# Filter-Stereo.net
KiCad netlist of a schematic drawn in Altium Designer
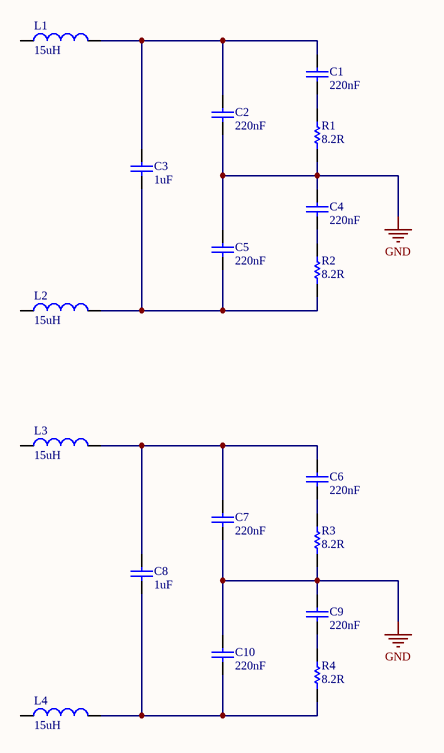
[diagram p0: Filter-Stereo.SchDoc]

(export (version "E")
  (design (tool "Eeschema 10.0.6"))
  (components
    (comp (ref "C1")
      (value "220nF")
      (footprint "CAP_RM15_W5L18")
      (description "CAP FILM 0.22UF 5% 100VDC RADIAL")
      (fields (field (name "MPN") "B32529C1224J289") (field (name "TOLERANCE") "5%"))
      (libsource (lib "micun") (part "CAP_B32529 _220nF"))
    )
    (comp (ref "C2")
      (value "220nF")
      (footprint "CAP_RM15_W5L18")
      (description "CAP FILM 0.22UF 5% 100VDC RADIAL")
      (fields (field (name "MPN") "B32529C1224J289") (field (name "TOLERANCE") "5%"))
      (libsource (lib "micun") (part "CAP_B32529 _220nF"))
    )
    (comp (ref "C3")
      (value "1uF")
      (footprint "CAP_RM5_W7.8L7.8H13")
      (description "CAP FILM 1UF 5% 100VDC RADIAL")
      (fields (field (name "MPN") "B32529D1105J289") (field (name "TOLERANCE") "5%"))
      (libsource (lib "micun") (part "CAP_B32529 _1uF"))
    )
    (comp (ref "C4")
      (value "220nF")
      (footprint "CAP_RM15_W5L18")
      (description "CAP FILM 0.22UF 5% 100VDC RADIAL")
      (fields (field (name "MPN") "B32529C1224J289") (field (name "TOLERANCE") "5%"))
      (libsource (lib "micun") (part "CAP_B32529 _220nF"))
    )
    (comp (ref "C5")
      (value "220nF")
      (footprint "CAP_RM15_W5L18")
      (description "CAP FILM 0.22UF 5% 100VDC RADIAL")
      (fields (field (name "MPN") "B32529C1224J289") (field (name "TOLERANCE") "5%"))
      (libsource (lib "micun") (part "CAP_B32529 _220nF"))
    )
    (comp (ref "C6")
      (value "220nF")
      (footprint "CAP_RM15_W5L18")
      (description "CAP FILM 0.22UF 5% 100VDC RADIAL")
      (fields (field (name "MPN") "B32529C1224J289") (field (name "TOLERANCE") "5%"))
      (libsource (lib "micun") (part "CAP_B32529 _220nF"))
    )
    (comp (ref "C7")
      (value "220nF")
      (footprint "CAP_RM15_W5L18")
      (description "CAP FILM 0.22UF 5% 100VDC RADIAL")
      (fields (field (name "MPN") "B32529C1224J289") (field (name "TOLERANCE") "5%"))
      (libsource (lib "micun") (part "CAP_B32529 _220nF"))
    )
    (comp (ref "C8")
      (value "1uF")
      (footprint "CAP_RM5_W7.8L7.8H13")
      (description "CAP FILM 1UF 5% 100VDC RADIAL")
      (fields (field (name "MPN") "B32529D1105J289") (field (name "TOLERANCE") "5%"))
      (libsource (lib "micun") (part "CAP_B32529 _1uF"))
    )
    (comp (ref "C9")
      (value "220nF")
      (footprint "CAP_RM15_W5L18")
      (description "CAP FILM 0.22UF 5% 100VDC RADIAL")
      (fields (field (name "MPN") "B32529C1224J289") (field (name "TOLERANCE") "5%"))
      (libsource (lib "micun") (part "CAP_B32529 _220nF"))
    )
    (comp (ref "C10")
      (value "220nF")
      (footprint "CAP_RM15_W5L18")
      (description "CAP FILM 0.22UF 5% 100VDC RADIAL")
      (fields (field (name "MPN") "B32529C1224J289") (field (name "TOLERANCE") "5%"))
      (libsource (lib "micun") (part "CAP_B32529 _220nF"))
    )
    (comp (ref "L1")
      (value "15uH")
      (footprint "1D14A")
      (description "Fixed Inductors Class D Inductor 15uH 16mOhms")
      (fields (field (name "MPN") "1D14A-150M") (field (name "Comment") "1D14A-150m"))
      (libsource (lib "micun") (part "L_1D14A-150m"))
    )
    (comp (ref "L2")
      (value "15uH")
      (footprint "1D14A")
      (description "Fixed Inductors Class D Inductor 15uH 16mOhms")
      (fields (field (name "MPN") "1D14A-150M") (field (name "Comment") "1D14A-150m"))
      (libsource (lib "micun") (part "L_1D14A-150m"))
    )
    (comp (ref "L3")
      (value "15uH")
      (footprint "1D14A")
      (description "Fixed Inductors Class D Inductor 15uH 16mOhms")
      (fields (field (name "MPN") "1D14A-150M") (field (name "Comment") "1D14A-150m"))
      (libsource (lib "micun") (part "L_1D14A-150m"))
    )
    (comp (ref "L4")
      (value "15uH")
      (footprint "1D14A")
      (description "Fixed Inductors Class D Inductor 15uH 16mOhms")
      (fields (field (name "MPN") "1D14A-150M") (field (name "Comment") "1D14A-150m"))
      (libsource (lib "micun") (part "L_1D14A-150m"))
    )
    (comp (ref "R1")
      (value "8.2R")
      (footprint "RESC1020")
      (fields
        (field (name "TOLERANCE") "±5%")
        (field (name "POWER") "2W")
        (field (name "MPN") "ERJ-B1BJ8R2U")
      )
      (libsource (lib "micun") (part "RES_ERJ-B1BJ8R2U"))
    )
    (comp (ref "R2")
      (value "8.2R")
      (footprint "RESC1020")
      (fields
        (field (name "TOLERANCE") "±5%")
        (field (name "POWER") "2W")
        (field (name "MPN") "ERJ-B1BJ8R2U")
      )
      (libsource (lib "micun") (part "RES_ERJ-B1BJ8R2U"))
    )
    (comp (ref "R3")
      (value "8.2R")
      (footprint "RESC1020")
      (fields
        (field (name "TOLERANCE") "±5%")
        (field (name "POWER") "2W")
        (field (name "MPN") "ERJ-B1BJ8R2U")
      )
      (libsource (lib "micun") (part "RES_ERJ-B1BJ8R2U"))
    )
    (comp (ref "R4")
      (value "8.2R")
      (footprint "RESC1020")
      (fields
        (field (name "TOLERANCE") "±5%")
        (field (name "POWER") "2W")
        (field (name "MPN") "ERJ-B1BJ8R2U")
      )
      (libsource (lib "micun") (part "RES_ERJ-B1BJ8R2U"))
    )
  )
  (nets
    (net (code "1") (name "GND") (class "Default")
      (node (ref "C10") (pin "2") (pinfunction "2_2") (pintype "passive"))
      (node (ref "C2") (pin "1") (pinfunction "1_1") (pintype "passive"))
      (node (ref "C4") (pin "2") (pinfunction "2_2") (pintype "passive"))
      (node (ref "C5") (pin "2") (pinfunction "2_2") (pintype "passive"))
      (node (ref "C7") (pin "1") (pinfunction "1_1") (pintype "passive"))
      (node (ref "C9") (pin "2") (pinfunction "2_2") (pintype "passive"))
      (node (ref "R1") (pin "1") (pinfunction "1_1") (pintype "passive"))
      (node (ref "R3") (pin "1") (pinfunction "1_1") (pintype "passive"))
    )
    (net (code "2") (name "Net-(C1-Pad1)") (class "Default")
      (node (ref "C1") (pin "1") (pinfunction "1_1") (pintype "passive"))
      (node (ref "R1") (pin "2") (pinfunction "2_2") (pintype "passive"))
    )
    (net (code "3") (name "Net-(C1-Pad2)") (class "Default")
      (node (ref "C1") (pin "2") (pinfunction "2_2") (pintype "passive"))
      (node (ref "C2") (pin "2") (pinfunction "2_2") (pintype "passive"))
      (node (ref "C3") (pin "2") (pinfunction "2_2") (pintype "passive"))
      (node (ref "L1") (pin "2") (pinfunction "2_2") (pintype "passive"))
    )
    (net (code "4") (name "Net-(C3-Pad1)") (class "Default")
      (node (ref "C3") (pin "1") (pinfunction "1_1") (pintype "passive"))
      (node (ref "C5") (pin "1") (pinfunction "1_1") (pintype "passive"))
      (node (ref "L2") (pin "2") (pinfunction "2_2") (pintype "passive"))
      (node (ref "R2") (pin "1") (pinfunction "1_1") (pintype "passive"))
    )
    (net (code "5") (name "Net-(C4-Pad1)") (class "Default")
      (node (ref "C4") (pin "1") (pinfunction "1_1") (pintype "passive"))
      (node (ref "R2") (pin "2") (pinfunction "2_2") (pintype "passive"))
    )
    (net (code "6") (name "Net-(C6-Pad1)") (class "Default")
      (node (ref "C6") (pin "1") (pinfunction "1_1") (pintype "passive"))
      (node (ref "R3") (pin "2") (pinfunction "2_2") (pintype "passive"))
    )
    (net (code "7") (name "Net-(C6-Pad2)") (class "Default")
      (node (ref "C6") (pin "2") (pinfunction "2_2") (pintype "passive"))
      (node (ref "C7") (pin "2") (pinfunction "2_2") (pintype "passive"))
      (node (ref "C8") (pin "2") (pinfunction "2_2") (pintype "passive"))
      (node (ref "L3") (pin "2") (pinfunction "2_2") (pintype "passive"))
    )
    (net (code "8") (name "Net-(C9-Pad1)") (class "Default")
      (node (ref "C9") (pin "1") (pinfunction "1_1") (pintype "passive"))
      (node (ref "R4") (pin "2") (pinfunction "2_2") (pintype "passive"))
    )
    (net (code "9") (name "Net-(C10-Pad1)") (class "Default")
      (node (ref "C10") (pin "1") (pinfunction "1_1") (pintype "passive"))
      (node (ref "C8") (pin "1") (pinfunction "1_1") (pintype "passive"))
      (node (ref "L4") (pin "2") (pinfunction "2_2") (pintype "passive"))
      (node (ref "R4") (pin "1") (pinfunction "1_1") (pintype "passive"))
    )
    (net (code "10") (name "unconnected-(L1-Pad1)") (class "Default")
      (node (ref "L1") (pin "1") (pinfunction "1_1") (pintype "passive"))
    )
    (net (code "11") (name "unconnected-(L2-Pad1)") (class "Default")
      (node (ref "L2") (pin "1") (pinfunction "1_1") (pintype "passive"))
    )
    (net (code "12") (name "unconnected-(L3-Pad1)") (class "Default")
      (node (ref "L3") (pin "1") (pinfunction "1_1") (pintype "passive"))
    )
    (net (code "13") (name "unconnected-(L4-Pad1)") (class "Default")
      (node (ref "L4") (pin "1") (pinfunction "1_1") (pintype "passive"))
    )
  )
)
